# MCU.net
KiCad netlist of a schematic drawn in Altium Designer
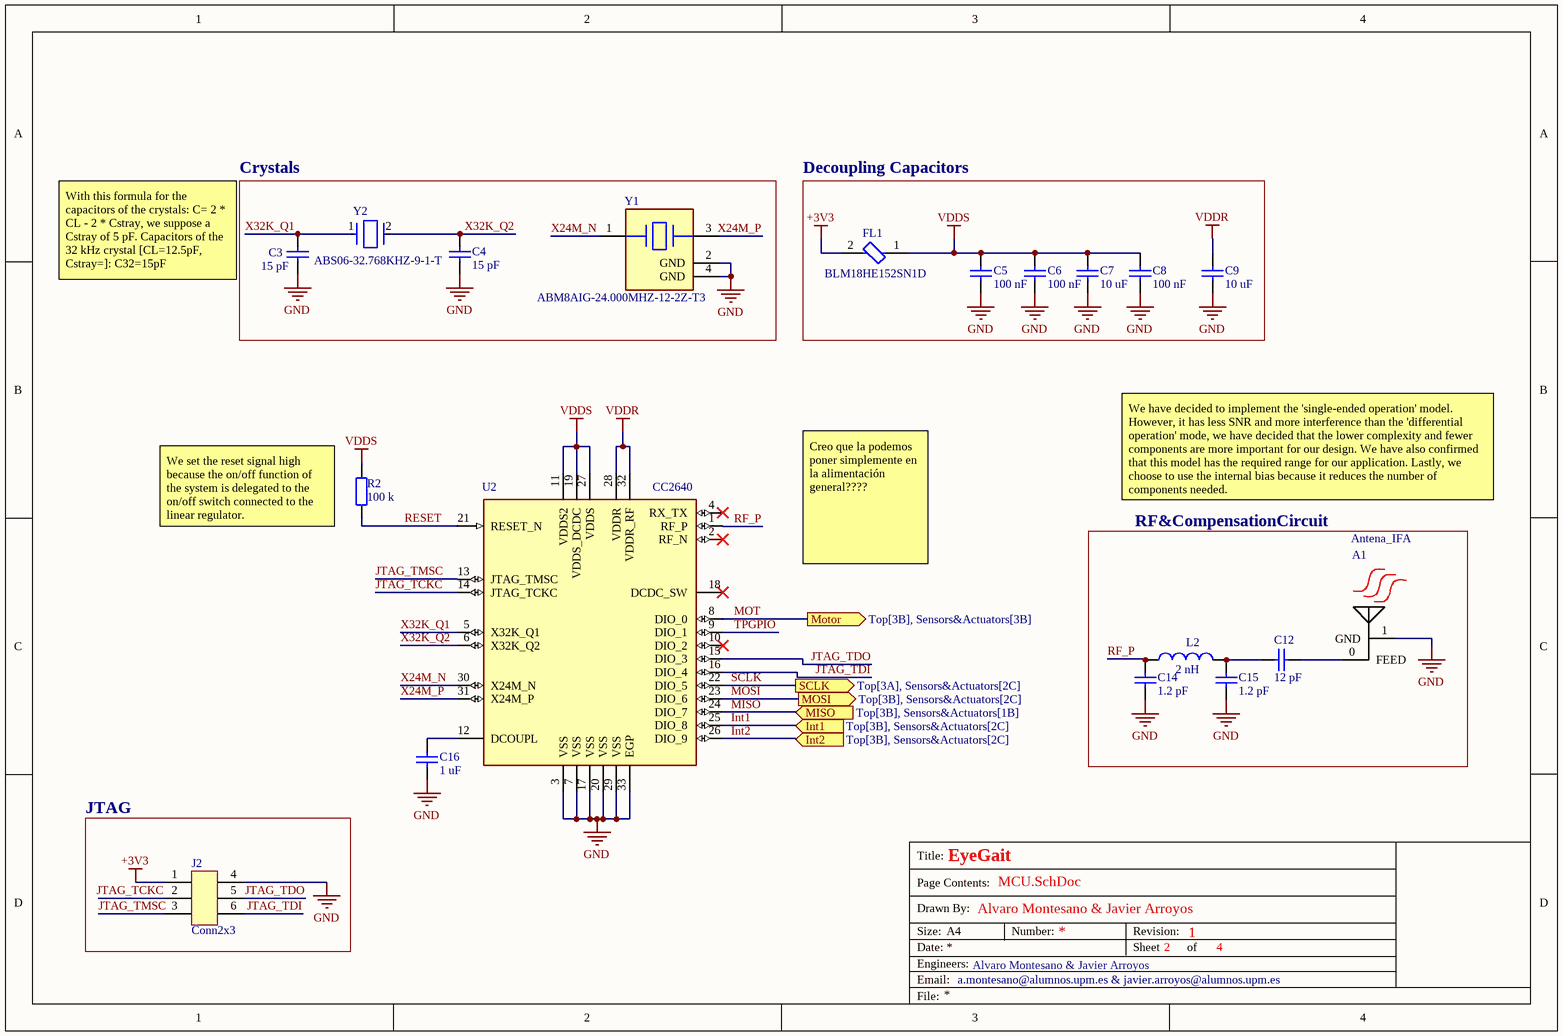
[diagram p0: MCU.SchDoc]

(export (version "E")
  (design (tool "Eeschema 10.0.6"))
  (components
    (comp (ref "A1")
      (value "Antena_IFA")
      (footprint "ANTENA_IFA")
      (libsource (lib "DEOP2324") (part "Antena_IFA"))
    )
    (comp (ref "C3")
      (value "15 pF")
      (footprint "C0402")
      (description "Capacitor")
      (libsource (lib "DEOP2324") (part "C"))
    )
    (comp (ref "C4")
      (value "15 pF")
      (footprint "C0402")
      (description "Capacitor")
      (libsource (lib "DEOP2324") (part "C"))
    )
    (comp (ref "C5")
      (value "100 nF")
      (footprint "C0402")
      (description "Capacitor")
      (libsource (lib "DEOP2324") (part "C"))
    )
    (comp (ref "C6")
      (value "100 nF")
      (footprint "C0402")
      (description "Capacitor")
      (libsource (lib "DEOP2324") (part "C"))
    )
    (comp (ref "C7")
      (value "10 uF")
      (footprint "C0402")
      (description "Capacitor")
      (libsource (lib "DEOP2324") (part "C"))
    )
    (comp (ref "C8")
      (value "100 nF")
      (footprint "C0402")
      (description "Capacitor")
      (libsource (lib "DEOP2324") (part "C"))
    )
    (comp (ref "C9")
      (value "10 uF")
      (footprint "C0402")
      (description "Capacitor")
      (libsource (lib "DEOP2324") (part "C"))
    )
    (comp (ref "C12")
      (value "12 pF")
      (footprint "C0402")
      (description "Capacitor")
      (libsource (lib "DEOP2324") (part "C"))
    )
    (comp (ref "C14")
      (value "1.2 pF")
      (footprint "C0402")
      (description "Capacitor")
      (libsource (lib "DEOP2324") (part "C"))
    )
    (comp (ref "C15")
      (value "1.2 pF")
      (footprint "C0402")
      (description "Capacitor")
      (libsource (lib "DEOP2324") (part "C"))
    )
    (comp (ref "C16")
      (value "1 uF")
      (footprint "C0402")
      (description "Capacitor")
      (libsource (lib "DEOP2324") (part "C"))
    )
    (comp (ref "FL1")
      (value "BLM18HE152SN1D")
      (footprint "FP-BLM18-0_15-t0_8-IPC_C")
      (description "Chip Ferrite Bead, 0603, 1500Ω @ 100MHz, 0.5Ω, 25%, 500mA")
      (fields (field (name "TOLERANCE") "25%"))
      (libsource (lib "Altium Content Vault") (part "5f30dd21d616792df468990f7003faa"))
    )
    (comp (ref "J2")
      (value "Conn2x3")
      (footprint "Pogo_6pins_minimum")
      (description "2x3 pin Terminal")
      (libsource (lib "DEOP2324") (part "Conn2x3"))
    )
    (comp (ref "L2")
      (value "2 nH")
      (footprint "L0402")
      (description "Inductor")
      (libsource (lib "DEOP2324") (part "L"))
    )
    (comp (ref "R2")
      (value "100 k")
      (footprint "R0402")
      (description "Resistor")
      (libsource (lib "DEOP2324") (part "R"))
    )
    (comp (ref "U2")
      (value "CC2640")
      (footprint "CC2640R2FRSM")
      (description "IC RF TXRX+MCU BLUETOOTH 32VFQFN")
      (fields (field (name "PART NUMBER") "CC2640R2FRSM") (field (name "MANUFACTURER") "Texas Instruments"))
      (libsource (lib "DEOP2324") (part "CC2640"))
    )
    (comp (ref "Y1")
      (value "ABM8AIG-24.000MHZ-12-2Z-T3")
      (footprint "FP-ABM8AIG-MFG")
      (description "Crystal 24MHz ±20ppm (Tol) ±50ppm (Stability) 12pF FUND 50Ω Automotive 4-Pin Ultra Mini-CSMD T/R")
      (libsource (lib "Altium Content Vault") (part "5645ab55de99a04feaa93ac4102b7fe"))
    )
    (comp (ref "Y2")
      (value "ABS06-32.768KHZ-9-1-T")
      (footprint "FP-ABS06-MFG")
      (description "Crystal 32.768kHz ±10ppm (Tol) 9pF FUND 90kΩ 2-Pin Mini-CSMD T/R")
      (fields (field (name "TOLERANCE") "10ppm"))
      (libsource (lib "Altium Content Vault") (part "c23a69dc6c9e2f18f2079038eb95dd1"))
    )
  )
  (nets
    (net (code "1") (name "+3V3") (class "Default")
      (node (ref "FL1") (pin "2") (pinfunction "2_2") (pintype "passive"))
      (node (ref "J2") (pin "1") (pinfunction "1_1") (pintype "passive"))
    )
    (net (code "2") (name "/Int1") (class "Default")
      (node (ref "U2") (pin "25") (pinfunction "DIO_8_25") (pintype "bidirectional"))
    )
    (net (code "3") (name "/Int2") (class "Default")
      (node (ref "U2") (pin "26") (pinfunction "DIO_9_26") (pintype "bidirectional"))
    )
    (net (code "4") (name "/JTAG_TCKC") (class "Default")
      (node (ref "J2") (pin "2") (pinfunction "2_2") (pintype "passive"))
      (node (ref "U2") (pin "14") (pinfunction "JTAG_TCKC_14") (pintype "bidirectional"))
    )
    (net (code "5") (name "/JTAG_TDI") (class "Default")
      (node (ref "J2") (pin "6") (pinfunction "6_6") (pintype "passive"))
      (node (ref "U2") (pin "16") (pinfunction "DIO_4_16") (pintype "bidirectional"))
    )
    (net (code "6") (name "/JTAG_TDO") (class "Default")
      (node (ref "J2") (pin "5") (pinfunction "5_5") (pintype "passive"))
      (node (ref "U2") (pin "15") (pinfunction "DIO_3_15") (pintype "bidirectional"))
    )
    (net (code "7") (name "/JTAG_TMSC") (class "Default")
      (node (ref "J2") (pin "3") (pinfunction "3_3") (pintype "passive"))
      (node (ref "U2") (pin "13") (pinfunction "JTAG_TMSC_13") (pintype "bidirectional"))
    )
    (net (code "8") (name "/MISO") (class "Default")
      (node (ref "U2") (pin "24") (pinfunction "DIO_7_24") (pintype "bidirectional"))
    )
    (net (code "9") (name "/MOSI") (class "Default")
      (node (ref "U2") (pin "23") (pinfunction "DIO_6_23") (pintype "bidirectional"))
    )
    (net (code "11") (name "/Motor") (class "Default")
      (node (ref "U2") (pin "8") (pinfunction "DIO_0_8") (pintype "bidirectional"))
    )
    (net (code "13") (name "/RESET") (class "Default")
      (node (ref "R2") (pin "2") (pinfunction "2_2") (pintype "passive"))
      (node (ref "U2") (pin "21") (pinfunction "RESET_N_21") (pintype "input"))
    )
    (net (code "14") (name "/RF_P") (class "Default")
      (node (ref "C14") (pin "2") (pinfunction "2_2") (pintype "passive"))
      (node (ref "L2") (pin "1") (pinfunction "1_1") (pintype "passive"))
      (node (ref "U2") (pin "1") (pinfunction "RF_P_1") (pintype "bidirectional"))
    )
    (net (code "15") (name "/SCLK") (class "Default")
      (node (ref "U2") (pin "22") (pinfunction "DIO_5_22") (pintype "bidirectional"))
    )
    (net (code "16") (name "/TPGPIO") (class "Default")
      (node (ref "U2") (pin "9") (pinfunction "DIO_1_9") (pintype "bidirectional"))
    )
    (net (code "17") (name "/X24M_N") (class "Default")
      (node (ref "U2") (pin "30") (pinfunction "X24M_N_30") (pintype "bidirectional"))
      (node (ref "Y1") (pin "1") (pinfunction "1_1") (pintype "passive"))
    )
    (net (code "18") (name "/X24M_P") (class "Default")
      (node (ref "U2") (pin "31") (pinfunction "X24M_P_31") (pintype "bidirectional"))
      (node (ref "Y1") (pin "3") (pinfunction "3_3") (pintype "passive"))
    )
    (net (code "19") (name "/X32K_Q1") (class "Default")
      (node (ref "C3") (pin "2") (pinfunction "2_2") (pintype "passive"))
      (node (ref "U2") (pin "5") (pinfunction "X32K_Q1_5") (pintype "bidirectional"))
      (node (ref "Y2") (pin "1") (pinfunction "1_1") (pintype "passive"))
    )
    (net (code "20") (name "/X32K_Q2") (class "Default")
      (node (ref "C4") (pin "2") (pinfunction "2_2") (pintype "passive"))
      (node (ref "U2") (pin "6") (pinfunction "X32K_Q2_6") (pintype "bidirectional"))
      (node (ref "Y2") (pin "2") (pinfunction "2_2") (pintype "passive"))
    )
    (net (code "21") (name "GND") (class "Default")
      (node (ref "A1") (pin "1") (pinfunction "GND_1") (pintype "power_in"))
      (node (ref "C14") (pin "1") (pinfunction "1_1") (pintype "passive"))
      (node (ref "C15") (pin "1") (pinfunction "1_1") (pintype "passive"))
      (node (ref "C16") (pin "1") (pinfunction "1_1") (pintype "passive"))
      (node (ref "C3") (pin "1") (pinfunction "1_1") (pintype "passive"))
      (node (ref "C4") (pin "1") (pinfunction "1_1") (pintype "passive"))
      (node (ref "C5") (pin "2") (pinfunction "2_2") (pintype "passive"))
      (node (ref "C6") (pin "2") (pinfunction "2_2") (pintype "passive"))
      (node (ref "C7") (pin "2") (pinfunction "2_2") (pintype "passive"))
      (node (ref "C8") (pin "2") (pinfunction "2_2") (pintype "passive"))
      (node (ref "C9") (pin "2") (pinfunction "2_2") (pintype "passive"))
      (node (ref "J2") (pin "4") (pinfunction "4_4") (pintype "passive"))
      (node (ref "U2") (pin "17") (pinfunction "VSS_17") (pintype "power_in"))
      (node (ref "U2") (pin "20") (pinfunction "VSS_20") (pintype "power_in"))
      (node (ref "U2") (pin "29") (pinfunction "VSS_29") (pintype "power_in"))
      (node (ref "U2") (pin "3") (pinfunction "VSS_3") (pintype "power_in"))
      (node (ref "U2") (pin "33") (pinfunction "EGP_33") (pintype "power_in"))
      (node (ref "U2") (pin "7") (pinfunction "VSS_7") (pintype "power_in"))
      (node (ref "Y1") (pin "2") (pinfunction "GND_2") (pintype "power_in"))
      (node (ref "Y1") (pin "4") (pinfunction "GND_4") (pintype "power_in"))
    )
    (net (code "22") (name "Net-(A1-FEED)") (class "Default")
      (node (ref "A1") (pin "0") (pinfunction "FEED_0") (pintype "passive"))
      (node (ref "C12") (pin "2") (pinfunction "2_2") (pintype "passive"))
    )
    (net (code "23") (name "Net-(C12-Pad1)") (class "Default")
      (node (ref "C12") (pin "1") (pinfunction "1_1") (pintype "passive"))
      (node (ref "C15") (pin "2") (pinfunction "2_2") (pintype "passive"))
      (node (ref "L2") (pin "2") (pinfunction "2_2") (pintype "passive"))
    )
    (net (code "24") (name "Net-(U2-DCOUPL)") (class "Default")
      (node (ref "C16") (pin "2") (pinfunction "2_2") (pintype "passive"))
      (node (ref "U2") (pin "12") (pinfunction "DCOUPL_12") (pintype "power_in"))
    )
    (net (code "25") (name "VDDR") (class "Default")
      (node (ref "C9") (pin "1") (pinfunction "1_1") (pintype "passive"))
      (node (ref "U2") (pin "28") (pinfunction "VDDR_28") (pintype "power_in"))
      (node (ref "U2") (pin "32") (pinfunction "VDDR_RF_32") (pintype "power_in"))
    )
    (net (code "26") (name "VDDS") (class "Default")
      (node (ref "C5") (pin "1") (pinfunction "1_1") (pintype "passive"))
      (node (ref "C6") (pin "1") (pinfunction "1_1") (pintype "passive"))
      (node (ref "C7") (pin "1") (pinfunction "1_1") (pintype "passive"))
      (node (ref "C8") (pin "1") (pinfunction "1_1") (pintype "passive"))
      (node (ref "FL1") (pin "1") (pinfunction "1_1") (pintype "passive"))
      (node (ref "R2") (pin "1") (pinfunction "1_1") (pintype "passive"))
      (node (ref "U2") (pin "11") (pinfunction "VDDS2_11") (pintype "power_in"))
      (node (ref "U2") (pin "19") (pinfunction "VDDS_DCDC_19") (pintype "power_in"))
      (node (ref "U2") (pin "27") (pinfunction "VDDS_27") (pintype "power_in"))
    )
    (net (code "27") (name "unconnected-(U2-DCDC_SW-Pad18)") (class "Default")
      (node (ref "U2") (pin "18") (pinfunction "DCDC_SW_18") (pintype "power_in+no_connect"))
    )
    (net (code "28") (name "unconnected-(U2-DIO_2-Pad10)") (class "Default")
      (node (ref "U2") (pin "10") (pinfunction "DIO_2_10") (pintype "bidirectional"))
    )
    (net (code "29") (name "unconnected-(U2-RF_N-Pad2)") (class "Default")
      (node (ref "U2") (pin "2") (pinfunction "RF_N_2") (pintype "bidirectional+no_connect"))
    )
    (net (code "30") (name "unconnected-(U2-RX_TX-Pad4)") (class "Default")
      (node (ref "U2") (pin "4") (pinfunction "RX_TX_4") (pintype "bidirectional+no_connect"))
    )
  )
)
